# CAN.net
KiCad netlist of a schematic drawn in Altium Designer
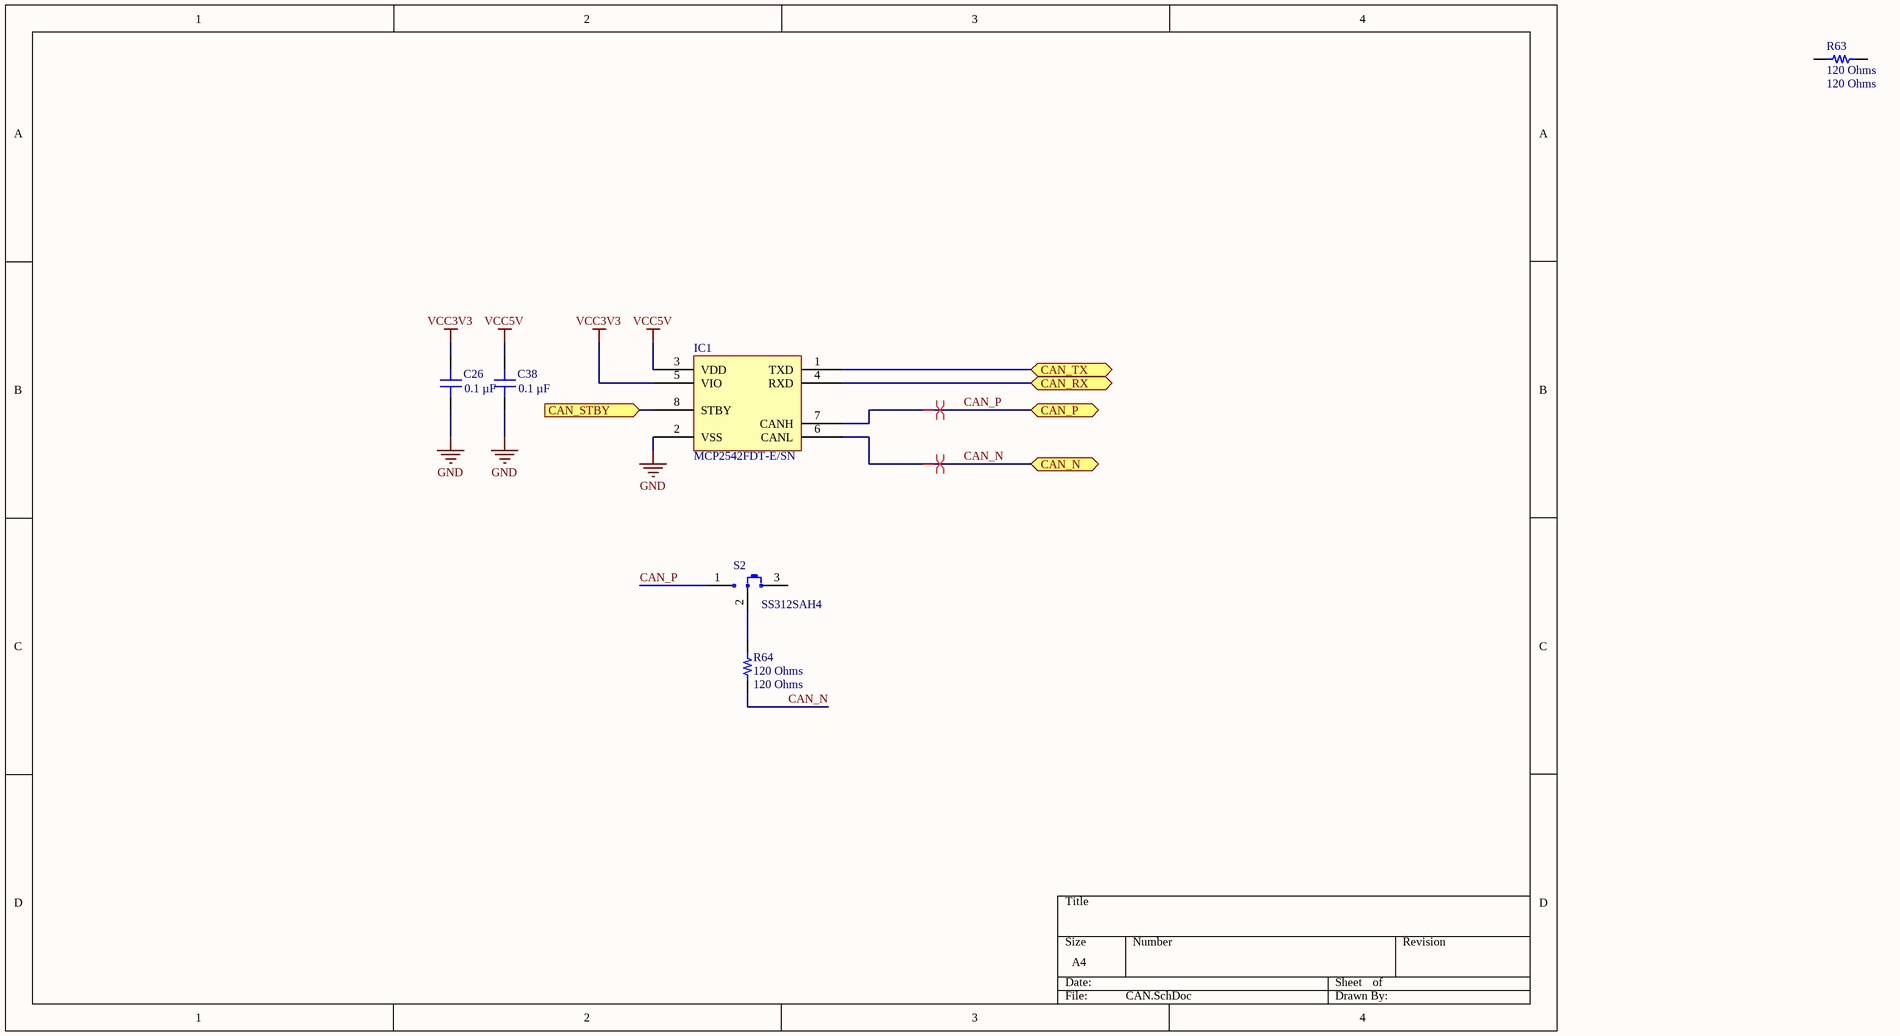
[diagram p0: CAN.SchDoc]

(export (version "E")
  (design (tool "Eeschema 10.0.6"))
  (components
    (comp (ref "C26")
      (value "0.1 µF")
      (footprint "CAP 0805_2012")
      (description "CAP CER 0.1UF 50V X7R 0805")
      (fields (field (name "PART NUMBER") "CC0805MRX7R9BB104") (field (name "MANUFACTURER") "Yageo"))
      (libsource (lib "Celestial Altium Library - altium_library") (part "Capacitor"))
    )
    (comp (ref "C38")
      (value "0.1 µF")
      (footprint "CAP 0805_2012")
      (description "CAP CER 0.1UF 50V X7R 0805")
      (fields (field (name "PART NUMBER") "CC0805MRX7R9BB104") (field (name "MANUFACTURER") "Yageo"))
      (libsource (lib "Celestial Altium Library - altium_library") (part "Capacitor"))
    )
    (comp (ref "IC1")
      (value "MCP2542FDT-E/SN")
      (footprint "MICROCHIP SOIC-8 150MIL WIDE")
      (description "IC TRANSCEIVER 1/1 8SOIC")
      (fields (field (name "MANUFACTURER") "Microchip Technology"))
      (libsource (lib "Celestial") (part "MICROCHIP MCP2542FD"))
    )
    (comp (ref "R63")
      (value "120 Ohms")
      (footprint "RES 0805_2012")
      (description "RES SMD 120 OHM 1% 1/8W 0805")
      (fields (field (name "PART NUMBER") "ERJ-6ENF1200V") (field (name "ALTIUM_VALUE") "120 Ohms"))
      (libsource (lib "Celestial Altium Library - altium_library") (part "Resistor"))
    )
    (comp (ref "R64")
      (value "120 Ohms")
      (footprint "RES 0805_2012")
      (description "RES SMD 120 OHM 1% 1/8W 0805")
      (fields (field (name "PART NUMBER") "ERJ-6ENF1200V") (field (name "ALTIUM_VALUE") "120 Ohms"))
      (libsource (lib "Celestial Altium Library - altium_library") (part "Resistor"))
    )
    (comp (ref "S2")
      (value "SS312SAH4")
      (footprint "NKK SS312SAH4")
      (description "SWITCH SLIDE SPDT 0.4VA 28V")
      (fields (field (name "MANUFACTURER") "NKK Switches"))
      (libsource (lib "CAL") (part "NKK SS312"))
    )
  )
  (nets
    (net (code "1") (name "/CAN_N") (class "Default")
      (node (ref "IC1") (pin "6") (pinfunction "CANL_6") (pintype "passive"))
      (node (ref "R64") (pin "1") (pinfunction "1_1") (pintype "passive"))
    )
    (net (code "2") (name "/CAN_P") (class "Default")
      (node (ref "IC1") (pin "7") (pinfunction "CANH_7") (pintype "passive"))
      (node (ref "S2") (pin "1") (pinfunction "1_1") (pintype "passive"))
    )
    (net (code "3") (name "/CAN_RX") (class "Default")
      (node (ref "IC1") (pin "4") (pinfunction "RXD_4") (pintype "passive"))
    )
    (net (code "4") (name "/CAN_STBY") (class "Default")
      (node (ref "IC1") (pin "8") (pinfunction "STBY_8") (pintype "passive"))
    )
    (net (code "5") (name "/CAN_TX") (class "Default")
      (node (ref "IC1") (pin "1") (pinfunction "TXD_1") (pintype "passive"))
    )
    (net (code "6") (name "GND") (class "Default")
      (node (ref "C26") (pin "1") (pinfunction "1_1") (pintype "passive"))
      (node (ref "C38") (pin "1") (pinfunction "1_1") (pintype "passive"))
      (node (ref "IC1") (pin "2") (pinfunction "VSS_2") (pintype "passive"))
    )
    (net (code "7") (name "Net-(S2-COM)") (class "Default")
      (node (ref "R64") (pin "2") (pinfunction "2_2") (pintype "passive"))
      (node (ref "S2") (pin "2") (pinfunction "COM_2") (pintype "passive"))
    )
    (net (code "8") (name "VCC3V3") (class "Default")
      (node (ref "C26") (pin "2") (pinfunction "2_2") (pintype "passive"))
      (node (ref "IC1") (pin "5") (pinfunction "VIO_5") (pintype "passive"))
    )
    (net (code "9") (name "VCC5V") (class "Default")
      (node (ref "C38") (pin "2") (pinfunction "2_2") (pintype "passive"))
      (node (ref "IC1") (pin "3") (pinfunction "VDD_3") (pintype "passive"))
    )
    (net (code "10") (name "unconnected-(R63-Pad1)") (class "Default")
      (node (ref "R63") (pin "1") (pinfunction "1_1") (pintype "passive"))
    )
    (net (code "11") (name "unconnected-(R63-Pad2)") (class "Default")
      (node (ref "R63") (pin "2") (pinfunction "2_2") (pintype "passive"))
    )
    (net (code "12") (name "unconnected-(S2-Pad3)") (class "Default")
      (node (ref "S2") (pin "3") (pinfunction "3_3") (pintype "passive"))
    )
  )
)
